# SOIC18.net
KiCad netlist of a schematic drawn in Altium Designer
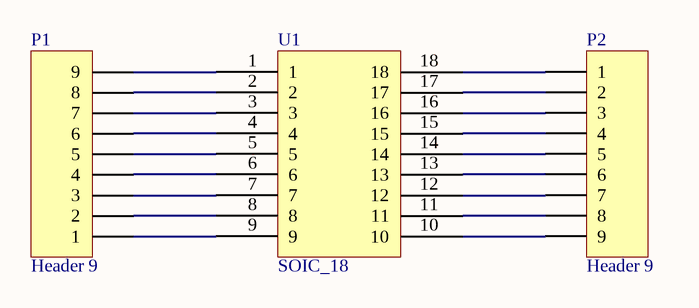
[diagram p0: SOIC18.SchDoc]

(export (version "E")
  (design (tool "Eeschema 10.0.6"))
  (components
    (comp (ref "P1")
      (value "Header 9")
      (footprint "HDR1X9")
      (description "Header, 9-Pin")
      (fields (field (name "PUBLISHER") "Altium Limited"))
      (libsource (lib "") (part "Header 9_1"))
    )
    (comp (ref "P2")
      (value "Header 9")
      (footprint "HDR1X9")
      (description "Header, 9-Pin")
      (fields (field (name "PUBLISHER") "Altium Limited"))
      (libsource (lib "Miscellaneous Connectors") (part "Header 9"))
    )
    (comp (ref "U1")
      (value "SOIC_18")
      (footprint "SOIC18")
      (libsource (lib "PCB_Breakout_Boards") (part "SOIC_18"))
    )
  )
  (nets
    (net (code "1") (name "Net-(P1-Pad1)") (class "Default")
      (node (ref "P1") (pin "1") (pinfunction "1_1") (pintype "passive"))
      (node (ref "U1") (pin "9") (pinfunction "9_9") (pintype "passive"))
    )
    (net (code "2") (name "Net-(P1-Pad2)") (class "Default")
      (node (ref "P1") (pin "2") (pinfunction "2_2") (pintype "passive"))
      (node (ref "U1") (pin "8") (pinfunction "8_8") (pintype "passive"))
    )
    (net (code "3") (name "Net-(P1-Pad3)") (class "Default")
      (node (ref "P1") (pin "3") (pinfunction "3_3") (pintype "passive"))
      (node (ref "U1") (pin "7") (pinfunction "7_7") (pintype "passive"))
    )
    (net (code "4") (name "Net-(P1-Pad4)") (class "Default")
      (node (ref "P1") (pin "4") (pinfunction "4_4") (pintype "passive"))
      (node (ref "U1") (pin "6") (pinfunction "6_6") (pintype "passive"))
    )
    (net (code "5") (name "Net-(P1-Pad5)") (class "Default")
      (node (ref "P1") (pin "5") (pinfunction "5_5") (pintype "passive"))
      (node (ref "U1") (pin "5") (pinfunction "5_5") (pintype "passive"))
    )
    (net (code "6") (name "Net-(P1-Pad6)") (class "Default")
      (node (ref "P1") (pin "6") (pinfunction "6_6") (pintype "passive"))
      (node (ref "U1") (pin "4") (pinfunction "4_4") (pintype "passive"))
    )
    (net (code "7") (name "Net-(P1-Pad7)") (class "Default")
      (node (ref "P1") (pin "7") (pinfunction "7_7") (pintype "passive"))
      (node (ref "U1") (pin "3") (pinfunction "3_3") (pintype "passive"))
    )
    (net (code "8") (name "Net-(P1-Pad8)") (class "Default")
      (node (ref "P1") (pin "8") (pinfunction "8_8") (pintype "passive"))
      (node (ref "U1") (pin "2") (pinfunction "2_2") (pintype "passive"))
    )
    (net (code "9") (name "Net-(P1-Pad9)") (class "Default")
      (node (ref "P1") (pin "9") (pinfunction "9_9") (pintype "passive"))
      (node (ref "U1") (pin "1") (pinfunction "1_1") (pintype "passive"))
    )
    (net (code "10") (name "Net-(P2-Pad1)") (class "Default")
      (node (ref "P2") (pin "1") (pinfunction "1_1") (pintype "passive"))
      (node (ref "U1") (pin "18") (pinfunction "18_18") (pintype "passive"))
    )
    (net (code "11") (name "Net-(P2-Pad2)") (class "Default")
      (node (ref "P2") (pin "2") (pinfunction "2_2") (pintype "passive"))
      (node (ref "U1") (pin "17") (pinfunction "17_17") (pintype "passive"))
    )
    (net (code "12") (name "Net-(P2-Pad3)") (class "Default")
      (node (ref "P2") (pin "3") (pinfunction "3_3") (pintype "passive"))
      (node (ref "U1") (pin "16") (pinfunction "16_16") (pintype "passive"))
    )
    (net (code "13") (name "Net-(P2-Pad4)") (class "Default")
      (node (ref "P2") (pin "4") (pinfunction "4_4") (pintype "passive"))
      (node (ref "U1") (pin "15") (pinfunction "15_15") (pintype "passive"))
    )
    (net (code "14") (name "Net-(P2-Pad5)") (class "Default")
      (node (ref "P2") (pin "5") (pinfunction "5_5") (pintype "passive"))
      (node (ref "U1") (pin "14") (pinfunction "14_14") (pintype "passive"))
    )
    (net (code "15") (name "Net-(P2-Pad6)") (class "Default")
      (node (ref "P2") (pin "6") (pinfunction "6_6") (pintype "passive"))
      (node (ref "U1") (pin "13") (pinfunction "13_13") (pintype "passive"))
    )
    (net (code "16") (name "Net-(P2-Pad7)") (class "Default")
      (node (ref "P2") (pin "7") (pinfunction "7_7") (pintype "passive"))
      (node (ref "U1") (pin "12") (pinfunction "12_12") (pintype "passive"))
    )
    (net (code "17") (name "Net-(P2-Pad8)") (class "Default")
      (node (ref "P2") (pin "8") (pinfunction "8_8") (pintype "passive"))
      (node (ref "U1") (pin "11") (pinfunction "11_11") (pintype "passive"))
    )
    (net (code "18") (name "Net-(P2-Pad9)") (class "Default")
      (node (ref "P2") (pin "9") (pinfunction "9_9") (pintype "passive"))
      (node (ref "U1") (pin "10") (pinfunction "10_10") (pintype "passive"))
    )
  )
)
